# fpga_power.net
KiCad netlist of a schematic drawn in Altium Designer
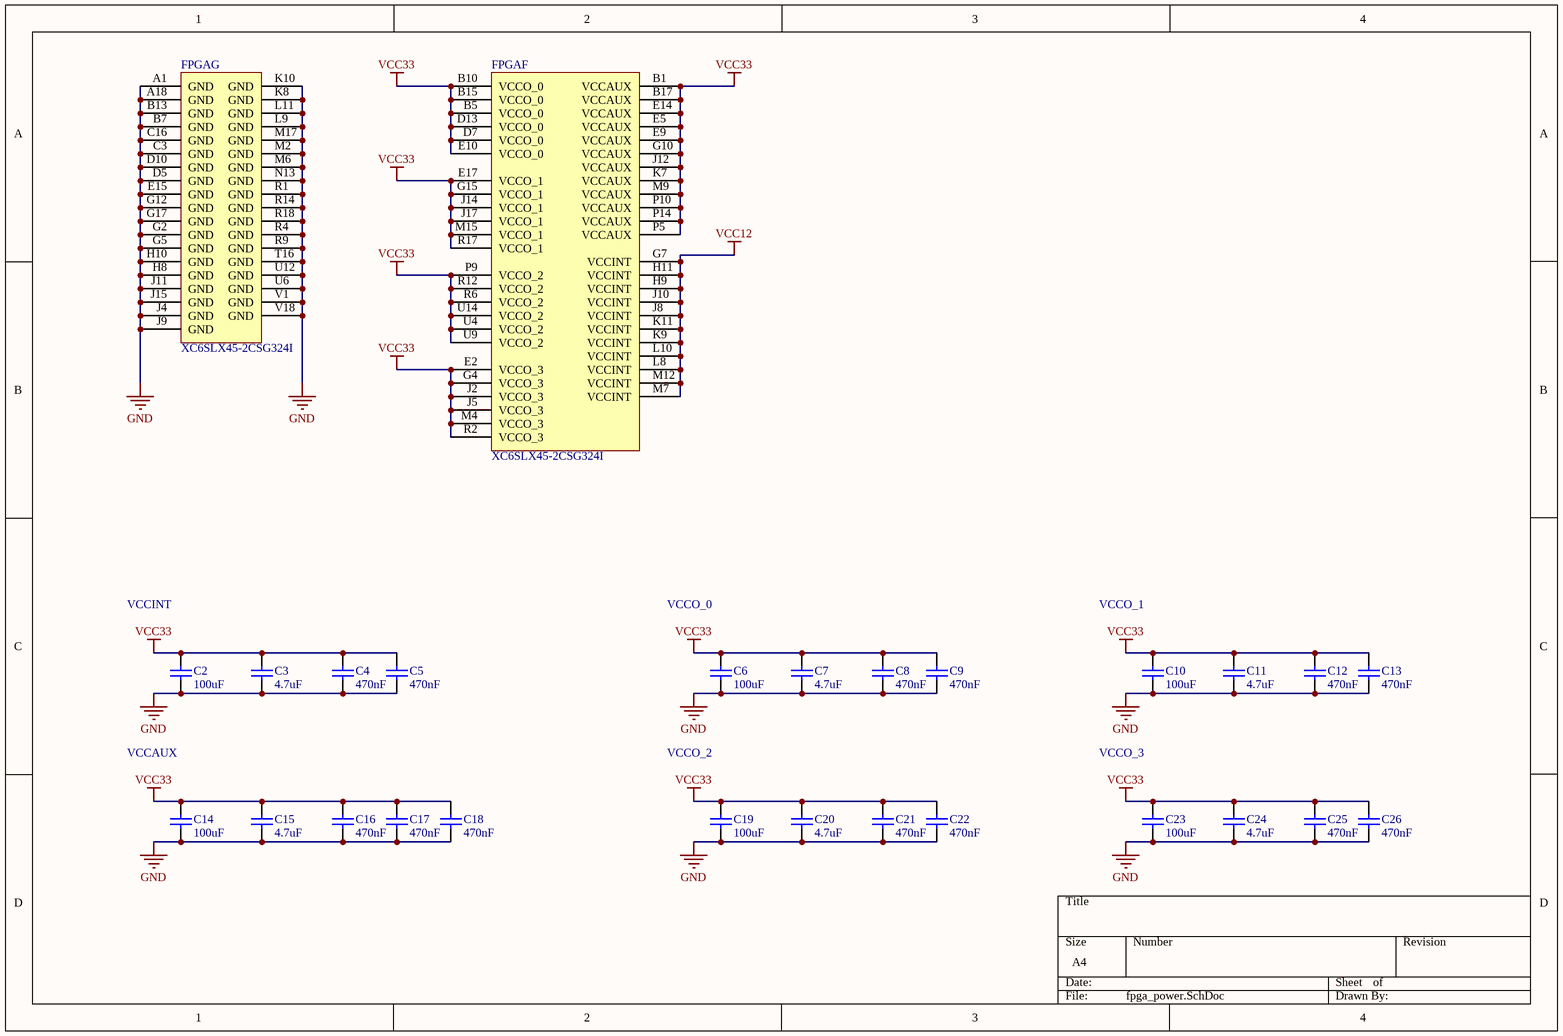
[diagram p0: fpga_power.SchDoc]

(export (version "E")
  (design (tool "Eeschema 10.0.6"))
  (components
    (comp (ref "C2")
      (value "100uF")
      (footprint "CAPC1210(3225)280A_M")
      (description "CAP 100uF 6.3V ±20% 1210 (3225 Metric) Thickness 2.8mm SMD")
      (fields (field (name "TOLERANCE") "±20%"))
      (libsource (lib "Altium Content Vault") (part "CMP-1038-02303-1"))
    )
    (comp (ref "C3")
      (value "4.7uF")
      (footprint "CAPC0805(2012)145_N")
      (description "CAP 4.7uF 10V ±10% 0805 (2012 Metric) Thickness 1.45mm SMD")
      (fields (field (name "TOLERANCE") "±10%"))
      (libsource (lib "Altium Content Vault") (part "CMP-1036-04881-1"))
    )
    (comp (ref "C4")
      (value "470nF")
      (footprint "CAPC0805(2012)100_N")
      (description "CAP 470nF 16V ±10% 0805 (2012 Metric) Thickness 1mm SMD")
      (fields (field (name "TOLERANCE") "±10%"))
      (libsource (lib "Altium Content Vault") (part "CMP-1036-04639-1"))
    )
    (comp (ref "C5")
      (value "470nF")
      (footprint "CAPC0805(2012)100_N")
      (description "CAP 470nF 16V ±10% 0805 (2012 Metric) Thickness 1mm SMD")
      (fields (field (name "TOLERANCE") "±10%"))
      (libsource (lib "Altium Content Vault") (part "CMP-1036-04639-1"))
    )
    (comp (ref "C6")
      (value "100uF")
      (footprint "CAPC1210(3225)280A_M")
      (description "CAP 100uF 6.3V ±20% 1210 (3225 Metric) Thickness 2.8mm SMD")
      (fields (field (name "TOLERANCE") "±20%"))
      (libsource (lib "Altium Content Vault") (part "CMP-1038-02303-1"))
    )
    (comp (ref "C7")
      (value "4.7uF")
      (footprint "CAPC0805(2012)145_N")
      (description "CAP 4.7uF 10V ±10% 0805 (2012 Metric) Thickness 1.45mm SMD")
      (fields (field (name "TOLERANCE") "±10%"))
      (libsource (lib "Altium Content Vault") (part "CMP-1036-04881-1"))
    )
    (comp (ref "C8")
      (value "470nF")
      (footprint "CAPC0805(2012)100_N")
      (description "CAP 470nF 16V ±10% 0805 (2012 Metric) Thickness 1mm SMD")
      (fields (field (name "TOLERANCE") "±10%"))
      (libsource (lib "Altium Content Vault") (part "CMP-1036-04639-1"))
    )
    (comp (ref "C9")
      (value "470nF")
      (footprint "CAPC0805(2012)100_N")
      (description "CAP 470nF 16V ±10% 0805 (2012 Metric) Thickness 1mm SMD")
      (fields (field (name "TOLERANCE") "±10%"))
      (libsource (lib "Altium Content Vault") (part "CMP-1036-04639-1"))
    )
    (comp (ref "C10")
      (value "100uF")
      (footprint "CAPC1210(3225)280A_M")
      (description "CAP 100uF 6.3V ±20% 1210 (3225 Metric) Thickness 2.8mm SMD")
      (fields (field (name "TOLERANCE") "±20%"))
      (libsource (lib "Altium Content Vault") (part "CMP-1038-02303-1"))
    )
    (comp (ref "C11")
      (value "4.7uF")
      (footprint "CAPC0805(2012)145_N")
      (description "CAP 4.7uF 10V ±10% 0805 (2012 Metric) Thickness 1.45mm SMD")
      (fields (field (name "TOLERANCE") "±10%"))
      (libsource (lib "Altium Content Vault") (part "CMP-1036-04881-1"))
    )
    (comp (ref "C12")
      (value "470nF")
      (footprint "CAPC0805(2012)100_N")
      (description "CAP 470nF 16V ±10% 0805 (2012 Metric) Thickness 1mm SMD")
      (fields (field (name "TOLERANCE") "±10%"))
      (libsource (lib "Altium Content Vault") (part "CMP-1036-04639-1"))
    )
    (comp (ref "C13")
      (value "470nF")
      (footprint "CAPC0805(2012)100_N")
      (description "CAP 470nF 16V ±10% 0805 (2012 Metric) Thickness 1mm SMD")
      (fields (field (name "TOLERANCE") "±10%"))
      (libsource (lib "Altium Content Vault") (part "CMP-1036-04639-1"))
    )
    (comp (ref "C14")
      (value "100uF")
      (footprint "CAPC1210(3225)280A_M")
      (description "CAP 100uF 6.3V ±20% 1210 (3225 Metric) Thickness 2.8mm SMD")
      (fields (field (name "TOLERANCE") "±20%"))
      (libsource (lib "Altium Content Vault") (part "CMP-1038-02303-1"))
    )
    (comp (ref "C15")
      (value "4.7uF")
      (footprint "CAPC0805(2012)145_N")
      (description "CAP 4.7uF 10V ±10% 0805 (2012 Metric) Thickness 1.45mm SMD")
      (fields (field (name "TOLERANCE") "±10%"))
      (libsource (lib "Altium Content Vault") (part "CMP-1036-04881-1"))
    )
    (comp (ref "C16")
      (value "470nF")
      (footprint "CAPC0805(2012)100_N")
      (description "CAP 470nF 16V ±10% 0805 (2012 Metric) Thickness 1mm SMD")
      (fields (field (name "TOLERANCE") "±10%"))
      (libsource (lib "Altium Content Vault") (part "CMP-1036-04639-1"))
    )
    (comp (ref "C17")
      (value "470nF")
      (footprint "CAPC0805(2012)100_N")
      (description "CAP 470nF 16V ±10% 0805 (2012 Metric) Thickness 1mm SMD")
      (fields (field (name "TOLERANCE") "±10%"))
      (libsource (lib "Altium Content Vault") (part "CMP-1036-04639-1"))
    )
    (comp (ref "C18")
      (value "470nF")
      (footprint "CAPC0805(2012)100_N")
      (description "CAP 470nF 16V ±10% 0805 (2012 Metric) Thickness 1mm SMD")
      (fields (field (name "TOLERANCE") "±10%"))
      (libsource (lib "Altium Content Vault") (part "CMP-1036-04639-1"))
    )
    (comp (ref "C19")
      (value "100uF")
      (footprint "CAPC1210(3225)280A_M")
      (description "CAP 100uF 6.3V ±20% 1210 (3225 Metric) Thickness 2.8mm SMD")
      (fields (field (name "TOLERANCE") "±20%"))
      (libsource (lib "Altium Content Vault") (part "CMP-1038-02303-1"))
    )
    (comp (ref "C20")
      (value "4.7uF")
      (footprint "CAPC0805(2012)145_N")
      (description "CAP 4.7uF 10V ±10% 0805 (2012 Metric) Thickness 1.45mm SMD")
      (fields (field (name "TOLERANCE") "±10%"))
      (libsource (lib "Altium Content Vault") (part "CMP-1036-04881-1"))
    )
    (comp (ref "C21")
      (value "470nF")
      (footprint "CAPC0805(2012)100_N")
      (description "CAP 470nF 16V ±10% 0805 (2012 Metric) Thickness 1mm SMD")
      (fields (field (name "TOLERANCE") "±10%"))
      (libsource (lib "Altium Content Vault") (part "CMP-1036-04639-1"))
    )
    (comp (ref "C22")
      (value "470nF")
      (footprint "CAPC0805(2012)100_N")
      (description "CAP 470nF 16V ±10% 0805 (2012 Metric) Thickness 1mm SMD")
      (fields (field (name "TOLERANCE") "±10%"))
      (libsource (lib "Altium Content Vault") (part "CMP-1036-04639-1"))
    )
    (comp (ref "C23")
      (value "100uF")
      (footprint "CAPC1210(3225)280A_M")
      (description "CAP 100uF 6.3V ±20% 1210 (3225 Metric) Thickness 2.8mm SMD")
      (fields (field (name "TOLERANCE") "±20%"))
      (libsource (lib "Altium Content Vault") (part "CMP-1038-02303-1"))
    )
    (comp (ref "C24")
      (value "4.7uF")
      (footprint "CAPC0805(2012)145_N")
      (description "CAP 4.7uF 10V ±10% 0805 (2012 Metric) Thickness 1.45mm SMD")
      (fields (field (name "TOLERANCE") "±10%"))
      (libsource (lib "Altium Content Vault") (part "CMP-1036-04881-1"))
    )
    (comp (ref "C25")
      (value "470nF")
      (footprint "CAPC0805(2012)100_N")
      (description "CAP 470nF 16V ±10% 0805 (2012 Metric) Thickness 1mm SMD")
      (fields (field (name "TOLERANCE") "±10%"))
      (libsource (lib "Altium Content Vault") (part "CMP-1036-04639-1"))
    )
    (comp (ref "C26")
      (value "470nF")
      (footprint "CAPC0805(2012)100_N")
      (description "CAP 470nF 16V ±10% 0805 (2012 Metric) Thickness 1mm SMD")
      (fields (field (name "TOLERANCE") "±10%"))
      (libsource (lib "Altium Content Vault") (part "CMP-1036-04639-1"))
    )
    (comp (ref "FPGA")
      (value "XC6SLX45-2CSG324I")
      (footprint "CSG324")
      (libsource (lib "Xilinx Spartan-6") (part "XC6SLX45-2CSG324I"))
    )
  )
  (nets
    (net (code "1") (name "GND") (class "Default")
      (node (ref "C10") (pin "1") (pinfunction "1_1") (pintype "passive"))
      (node (ref "C11") (pin "1") (pinfunction "1_1") (pintype "passive"))
      (node (ref "C12") (pin "1") (pinfunction "1_1") (pintype "passive"))
      (node (ref "C13") (pin "1") (pinfunction "1_1") (pintype "passive"))
      (node (ref "C14") (pin "1") (pinfunction "1_1") (pintype "passive"))
      (node (ref "C15") (pin "1") (pinfunction "1_1") (pintype "passive"))
      (node (ref "C16") (pin "1") (pinfunction "1_1") (pintype "passive"))
      (node (ref "C17") (pin "1") (pinfunction "1_1") (pintype "passive"))
      (node (ref "C18") (pin "1") (pinfunction "1_1") (pintype "passive"))
      (node (ref "C19") (pin "1") (pinfunction "1_1") (pintype "passive"))
      (node (ref "C2") (pin "1") (pinfunction "1_1") (pintype "passive"))
      (node (ref "C20") (pin "1") (pinfunction "1_1") (pintype "passive"))
      (node (ref "C21") (pin "1") (pinfunction "1_1") (pintype "passive"))
      (node (ref "C22") (pin "1") (pinfunction "1_1") (pintype "passive"))
      (node (ref "C23") (pin "1") (pinfunction "1_1") (pintype "passive"))
      (node (ref "C24") (pin "1") (pinfunction "1_1") (pintype "passive"))
      (node (ref "C25") (pin "1") (pinfunction "1_1") (pintype "passive"))
      (node (ref "C26") (pin "1") (pinfunction "1_1") (pintype "passive"))
      (node (ref "C3") (pin "1") (pinfunction "1_1") (pintype "passive"))
      (node (ref "C4") (pin "1") (pinfunction "1_1") (pintype "passive"))
      (node (ref "C5") (pin "1") (pinfunction "1_1") (pintype "passive"))
      (node (ref "C6") (pin "1") (pinfunction "1_1") (pintype "passive"))
      (node (ref "C7") (pin "1") (pinfunction "1_1") (pintype "passive"))
      (node (ref "C8") (pin "1") (pinfunction "1_1") (pintype "passive"))
      (node (ref "C9") (pin "1") (pinfunction "1_1") (pintype "passive"))
      (node (ref "FPGA") (pin "A1") (pinfunction "GND_A1") (pintype "power_in"))
      (node (ref "FPGA") (pin "A18") (pinfunction "GND_A18") (pintype "power_in"))
      (node (ref "FPGA") (pin "B13") (pinfunction "GND_B13") (pintype "power_in"))
      (node (ref "FPGA") (pin "B7") (pinfunction "GND_B7") (pintype "power_in"))
      (node (ref "FPGA") (pin "C16") (pinfunction "GND_C16") (pintype "power_in"))
      (node (ref "FPGA") (pin "C3") (pinfunction "GND_C3") (pintype "power_in"))
      (node (ref "FPGA") (pin "D10") (pinfunction "GND_D10") (pintype "power_in"))
      (node (ref "FPGA") (pin "D5") (pinfunction "GND_D5") (pintype "power_in"))
      (node (ref "FPGA") (pin "E15") (pinfunction "GND_E15") (pintype "power_in"))
      (node (ref "FPGA") (pin "G12") (pinfunction "GND_G12") (pintype "power_in"))
      (node (ref "FPGA") (pin "G17") (pinfunction "GND_G17") (pintype "power_in"))
      (node (ref "FPGA") (pin "G2") (pinfunction "GND_G2") (pintype "power_in"))
      (node (ref "FPGA") (pin "G5") (pinfunction "GND_G5") (pintype "power_in"))
      (node (ref "FPGA") (pin "H10") (pinfunction "GND_H10") (pintype "power_in"))
      (node (ref "FPGA") (pin "H8") (pinfunction "GND_H8") (pintype "power_in"))
      (node (ref "FPGA") (pin "J11") (pinfunction "GND_J11") (pintype "power_in"))
      (node (ref "FPGA") (pin "J15") (pinfunction "GND_J15") (pintype "power_in"))
      (node (ref "FPGA") (pin "J4") (pinfunction "GND_J4") (pintype "power_in"))
      (node (ref "FPGA") (pin "J9") (pinfunction "GND_J9") (pintype "power_in"))
      (node (ref "FPGA") (pin "K10") (pinfunction "GND_K10") (pintype "power_in"))
      (node (ref "FPGA") (pin "K8") (pinfunction "GND_K8") (pintype "power_in"))
      (node (ref "FPGA") (pin "L11") (pinfunction "GND_L11") (pintype "power_in"))
      (node (ref "FPGA") (pin "L9") (pinfunction "GND_L9") (pintype "power_in"))
      (node (ref "FPGA") (pin "M17") (pinfunction "GND_M17") (pintype "power_in"))
      (node (ref "FPGA") (pin "M2") (pinfunction "GND_M2") (pintype "power_in"))
      (node (ref "FPGA") (pin "M6") (pinfunction "GND_M6") (pintype "power_in"))
      (node (ref "FPGA") (pin "N13") (pinfunction "GND_N13") (pintype "power_in"))
      (node (ref "FPGA") (pin "R1") (pinfunction "GND_R1") (pintype "power_in"))
      (node (ref "FPGA") (pin "R14") (pinfunction "GND_R14") (pintype "power_in"))
      (node (ref "FPGA") (pin "R18") (pinfunction "GND_R18") (pintype "power_in"))
      (node (ref "FPGA") (pin "R4") (pinfunction "GND_R4") (pintype "power_in"))
      (node (ref "FPGA") (pin "R9") (pinfunction "GND_R9") (pintype "power_in"))
      (node (ref "FPGA") (pin "T16") (pinfunction "GND_T16") (pintype "power_in"))
      (node (ref "FPGA") (pin "U12") (pinfunction "GND_U12") (pintype "power_in"))
      (node (ref "FPGA") (pin "U6") (pinfunction "GND_U6") (pintype "power_in"))
      (node (ref "FPGA") (pin "V1") (pinfunction "GND_V1") (pintype "power_in"))
      (node (ref "FPGA") (pin "V18") (pinfunction "GND_V18") (pintype "power_in"))
    )
    (net (code "2") (name "VCC12") (class "Default")
      (node (ref "FPGA") (pin "G7") (pinfunction "VCCINT_G7") (pintype "power_in"))
      (node (ref "FPGA") (pin "H11") (pinfunction "VCCINT_H11") (pintype "power_in"))
      (node (ref "FPGA") (pin "H9") (pinfunction "VCCINT_H9") (pintype "power_in"))
      (node (ref "FPGA") (pin "J10") (pinfunction "VCCINT_J10") (pintype "power_in"))
      (node (ref "FPGA") (pin "J8") (pinfunction "VCCINT_J8") (pintype "power_in"))
      (node (ref "FPGA") (pin "K11") (pinfunction "VCCINT_K11") (pintype "power_in"))
      (node (ref "FPGA") (pin "K9") (pinfunction "VCCINT_K9") (pintype "power_in"))
      (node (ref "FPGA") (pin "L10") (pinfunction "VCCINT_L10") (pintype "power_in"))
      (node (ref "FPGA") (pin "L8") (pinfunction "VCCINT_L8") (pintype "power_in"))
      (node (ref "FPGA") (pin "M12") (pinfunction "VCCINT_M12") (pintype "power_in"))
      (node (ref "FPGA") (pin "M7") (pinfunction "VCCINT_M7") (pintype "power_in"))
    )
    (net (code "3") (name "VCC33") (class "Default")
      (node (ref "C10") (pin "2") (pinfunction "2_2") (pintype "passive"))
      (node (ref "C11") (pin "2") (pinfunction "2_2") (pintype "passive"))
      (node (ref "C12") (pin "2") (pinfunction "2_2") (pintype "passive"))
      (node (ref "C13") (pin "2") (pinfunction "2_2") (pintype "passive"))
      (node (ref "C14") (pin "2") (pinfunction "2_2") (pintype "passive"))
      (node (ref "C15") (pin "2") (pinfunction "2_2") (pintype "passive"))
      (node (ref "C16") (pin "2") (pinfunction "2_2") (pintype "passive"))
      (node (ref "C17") (pin "2") (pinfunction "2_2") (pintype "passive"))
      (node (ref "C18") (pin "2") (pinfunction "2_2") (pintype "passive"))
      (node (ref "C19") (pin "2") (pinfunction "2_2") (pintype "passive"))
      (node (ref "C2") (pin "2") (pinfunction "2_2") (pintype "passive"))
      (node (ref "C20") (pin "2") (pinfunction "2_2") (pintype "passive"))
      (node (ref "C21") (pin "2") (pinfunction "2_2") (pintype "passive"))
      (node (ref "C22") (pin "2") (pinfunction "2_2") (pintype "passive"))
      (node (ref "C23") (pin "2") (pinfunction "2_2") (pintype "passive"))
      (node (ref "C24") (pin "2") (pinfunction "2_2") (pintype "passive"))
      (node (ref "C25") (pin "2") (pinfunction "2_2") (pintype "passive"))
      (node (ref "C26") (pin "2") (pinfunction "2_2") (pintype "passive"))
      (node (ref "C3") (pin "2") (pinfunction "2_2") (pintype "passive"))
      (node (ref "C4") (pin "2") (pinfunction "2_2") (pintype "passive"))
      (node (ref "C5") (pin "2") (pinfunction "2_2") (pintype "passive"))
      (node (ref "C6") (pin "2") (pinfunction "2_2") (pintype "passive"))
      (node (ref "C7") (pin "2") (pinfunction "2_2") (pintype "passive"))
      (node (ref "C8") (pin "2") (pinfunction "2_2") (pintype "passive"))
      (node (ref "C9") (pin "2") (pinfunction "2_2") (pintype "passive"))
      (node (ref "FPGA") (pin "B1") (pinfunction "VCCAUX_B1") (pintype "power_in"))
      (node (ref "FPGA") (pin "B10") (pinfunction "VCCO_0_B10") (pintype "power_in"))
      (node (ref "FPGA") (pin "B15") (pinfunction "VCCO_0_B15") (pintype "power_in"))
      (node (ref "FPGA") (pin "B17") (pinfunction "VCCAUX_B17") (pintype "power_in"))
      (node (ref "FPGA") (pin "B5") (pinfunction "VCCO_0_B5") (pintype "power_in"))
      (node (ref "FPGA") (pin "D13") (pinfunction "VCCO_0_D13") (pintype "power_in"))
      (node (ref "FPGA") (pin "D7") (pinfunction "VCCO_0_D7") (pintype "power_in"))
      (node (ref "FPGA") (pin "E10") (pinfunction "VCCO_0_E10") (pintype "power_in"))
      (node (ref "FPGA") (pin "E14") (pinfunction "VCCAUX_E14") (pintype "power_in"))
      (node (ref "FPGA") (pin "E17") (pinfunction "VCCO_1_E17") (pintype "power_in"))
      (node (ref "FPGA") (pin "E2") (pinfunction "VCCO_3_E2") (pintype "power_in"))
      (node (ref "FPGA") (pin "E5") (pinfunction "VCCAUX_E5") (pintype "power_in"))
      (node (ref "FPGA") (pin "E9") (pinfunction "VCCAUX_E9") (pintype "power_in"))
      (node (ref "FPGA") (pin "G10") (pinfunction "VCCAUX_G10") (pintype "power_in"))
      (node (ref "FPGA") (pin "G15") (pinfunction "VCCO_1_G15") (pintype "power_in"))
      (node (ref "FPGA") (pin "G4") (pinfunction "VCCO_3_G4") (pintype "power_in"))
      (node (ref "FPGA") (pin "J12") (pinfunction "VCCAUX_J12") (pintype "power_in"))
      (node (ref "FPGA") (pin "J14") (pinfunction "VCCO_1_J14") (pintype "power_in"))
      (node (ref "FPGA") (pin "J17") (pinfunction "VCCO_1_J17") (pintype "power_in"))
      (node (ref "FPGA") (pin "J2") (pinfunction "VCCO_3_J2") (pintype "power_in"))
      (node (ref "FPGA") (pin "J5") (pinfunction "VCCO_3_J5") (pintype "power_in"))
      (node (ref "FPGA") (pin "K7") (pinfunction "VCCAUX_K7") (pintype "power_in"))
      (node (ref "FPGA") (pin "M15") (pinfunction "VCCO_1_M15") (pintype "power_in"))
      (node (ref "FPGA") (pin "M4") (pinfunction "VCCO_3_M4") (pintype "power_in"))
      (node (ref "FPGA") (pin "M9") (pinfunction "VCCAUX_M9") (pintype "power_in"))
      (node (ref "FPGA") (pin "P10") (pinfunction "VCCAUX_P10") (pintype "power_in"))
      (node (ref "FPGA") (pin "P14") (pinfunction "VCCAUX_P14") (pintype "power_in"))
      (node (ref "FPGA") (pin "P5") (pinfunction "VCCAUX_P5") (pintype "power_in"))
      (node (ref "FPGA") (pin "P9") (pinfunction "VCCO_2_P9") (pintype "power_in"))
      (node (ref "FPGA") (pin "R12") (pinfunction "VCCO_2_R12") (pintype "power_in"))
      (node (ref "FPGA") (pin "R17") (pinfunction "VCCO_1_R17") (pintype "power_in"))
      (node (ref "FPGA") (pin "R2") (pinfunction "VCCO_3_R2") (pintype "power_in"))
      (node (ref "FPGA") (pin "R6") (pinfunction "VCCO_2_R6") (pintype "power_in"))
      (node (ref "FPGA") (pin "U14") (pinfunction "VCCO_2_U14") (pintype "power_in"))
      (node (ref "FPGA") (pin "U4") (pinfunction "VCCO_2_U4") (pintype "power_in"))
      (node (ref "FPGA") (pin "U9") (pinfunction "VCCO_2_U9") (pintype "power_in"))
    )
  )
)
